# TM_Acondicionation.net
KiCad netlist of a schematic drawn in Altium Designer
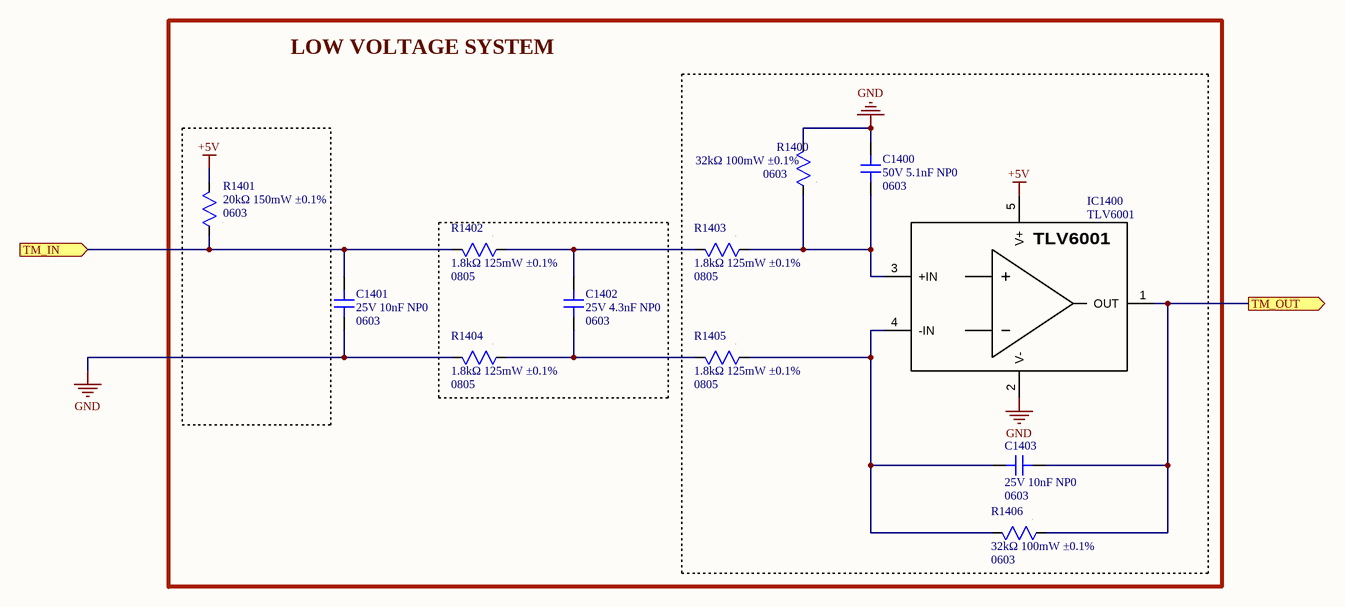
[diagram p0: TM_Acondicionation.SchDoc]

(export (version "E")
  (design (tool "Eeschema 10.0.6"))
  (components
    (comp (ref "C1400")
      (value "50V 5.1nF NP0")
      (footprint "CAP SMD 0603")
      (description "Condensadores de cerámica multicapa (MLCC- SMD/SMT) 50V 5100pF 0603 C0G 1%")
      (fields
        (field (name "PACKAGE") "0603")
        (field (name "MPN") "C0603C512F5GACTU")
        (field (name "MANUFACTURER") "KEMET")
      )
      (libsource (lib "eUSR_Database") (part "CAP non polarized"))
    )
    (comp (ref "C1401")
      (value "25V 10nF NP0")
      (footprint "CAP SMD 0603")
      (description "Condensadores de cerámica multicapa (MLCC- SMD/SMT) 50V 5100pF 0603 C0G 1%")
      (fields
        (field (name "PACKAGE") "0603")
        (field (name "MPN") "C0603C512F5GACTU")
        (field (name "MANUFACTURER") "KEMET")
      )
      (libsource (lib "eUSR_Database") (part "CAP non polarized"))
    )
    (comp (ref "C1402")
      (value "25V 4.3nF NP0")
      (footprint "CAP SMD 0603")
      (description "Condensadores de cerámica multicapa (MLCC- SMD/SMT) 4300 pF 25 VDC 2% 0603 C0G (NP0)")
      (fields
        (field (name "PACKAGE") "0603")
        (field (name "MPN") "GRM1885C1E432GA01J")
        (field (name "MANUFACTURER") "muRata")
      )
      (libsource (lib "eUSR_Database") (part "CAP non polarized"))
    )
    (comp (ref "C1403")
      (value "25V 10nF NP0")
      (footprint "CAP SMD 0603")
      (description "Condensadores de cerámica multicapa (MLCC- SMD/SMT) 0.01 uF 25 VDC 1% 0603 C0G (NP0) AEC-Q200")
      (fields
        (field (name "PACKAGE") "0603")
        (field (name "MPN") "GRT1885C1E103FA02D")
        (field (name "MANUFACTURER") "muRata")
      )
      (libsource (lib "eUSR_Database") (part "CAP non polarized"))
    )
    (comp (ref "IC1400")
      (value "TLV6001")
      (footprint "SOT-23-5")
      (fields (field (name "MPN") "TLV6001UIDBVR") (field (name "MANUFACTURER") "Texas Instruments"))
      (libsource (lib "eUSR_Database") (part "TLV6001"))
    )
    (comp (ref "R1400")
      (value "32kΩ 100mW ±0.1%")
      (footprint "RES SMD 0603")
      (description "Resistores de película fina - SMD 1/10W 32K Ohms 0.1%")
      (fields
        (field (name "PACKAGE") "0603")
        (field (name "MPN") "RT0603BRD0732KL")
        (field (name "MANUFACTURER") "YAGEO")
      )
      (libsource (lib "eUSR_Database") (part "RES"))
    )
    (comp (ref "R1401")
      (value "20kΩ 150mW ±0.1%")
      (footprint "RES SMD 0603")
      (description "Resistores de película fina - SMD RQ 0603 20K 0.1% 10PPM 5K RL")
      (fields
        (field (name "PACKAGE") "0603")
        (field (name "MPN") "RQ73C1J20KBTD")
        (field (name "MANUFACTURER") "TE Connectivity / Holsworthy")
      )
      (libsource (lib "eUSR_Database") (part "RES"))
    )
    (comp (ref "R1402")
      (value "1.8kΩ 125mW ±0.1%")
      (footprint "RES SMD 0805")
      (description "Thin Film Resistors 0805 1.8Kohm 0.1% 10ppm AEC-Q200")
      (fields
        (field (name "PACKAGE") "0805")
        (field (name "MPN") "ERA-6ARB182V")
        (field (name "MANUFACTURER") "Panasonic")
      )
      (libsource (lib "eUSR_Database") (part "RES"))
    )
    (comp (ref "R1403")
      (value "1.8kΩ 125mW ±0.1%")
      (footprint "RES SMD 0805")
      (description "Thin Film Resistors 0805 1.8Kohm 0.1% 10ppm AEC-Q200")
      (fields
        (field (name "PACKAGE") "0805")
        (field (name "MPN") "ERA-6ARB182V")
        (field (name "MANUFACTURER") "Panasonic")
      )
      (libsource (lib "eUSR_Database") (part "RES"))
    )
    (comp (ref "R1404")
      (value "1.8kΩ 125mW ±0.1%")
      (footprint "RES SMD 0805")
      (description "Thin Film Resistors 0805 1.8Kohm 0.1% 10ppm AEC-Q200")
      (fields
        (field (name "PACKAGE") "0805")
        (field (name "MPN") "ERA-6ARB182V")
        (field (name "MANUFACTURER") "Panasonic")
      )
      (libsource (lib "eUSR_Database") (part "RES"))
    )
    (comp (ref "R1405")
      (value "1.8kΩ 125mW ±0.1%")
      (footprint "RES SMD 0805")
      (description "Thin Film Resistors 0805 1.8Kohm 0.1% 10ppm AEC-Q200")
      (fields
        (field (name "PACKAGE") "0805")
        (field (name "MPN") "ERA-6ARB182V")
        (field (name "MANUFACTURER") "Panasonic")
      )
      (libsource (lib "eUSR_Database") (part "RES"))
    )
    (comp (ref "R1406")
      (value "32kΩ 100mW ±0.1%")
      (footprint "RES SMD 0603")
      (description "Resistores de película fina - SMD 1/10W 32K Ohms 0.1%")
      (fields
        (field (name "PACKAGE") "0603")
        (field (name "MPN") "RT0603BRD0732KL")
        (field (name "MANUFACTURER") "YAGEO")
      )
      (libsource (lib "eUSR_Database") (part "RES"))
    )
  )
  (nets
    (net (code "1") (name "+5V") (class "Default")
      (node (ref "IC1400") (pin "5") (pinfunction "V+_5") (pintype "passive"))
      (node (ref "R1401") (pin "2") (pinfunction "2_2") (pintype "passive"))
    )
    (net (code "2") (name "/TM_IN") (class "Default")
      (node (ref "C1401") (pin "1") (pinfunction "1_1") (pintype "passive"))
      (node (ref "R1401") (pin "1") (pinfunction "1_1") (pintype "passive"))
      (node (ref "R1402") (pin "2") (pinfunction "2_2") (pintype "passive"))
    )
    (net (code "3") (name "/TM_OUT") (class "Default")
      (node (ref "C1403") (pin "2") (pinfunction "2_2") (pintype "passive"))
      (node (ref "IC1400") (pin "1") (pinfunction "OUT_1") (pintype "passive"))
      (node (ref "R1406") (pin "1") (pinfunction "1_1") (pintype "passive"))
    )
    (net (code "4") (name "GND") (class "Default")
      (node (ref "C1400") (pin "1") (pinfunction "1_1") (pintype "passive"))
      (node (ref "C1401") (pin "2") (pinfunction "2_2") (pintype "passive"))
      (node (ref "IC1400") (pin "2") (pinfunction "V-_2") (pintype "passive"))
      (node (ref "R1400") (pin "2") (pinfunction "2_2") (pintype "passive"))
      (node (ref "R1404") (pin "2") (pinfunction "2_2") (pintype "passive"))
    )
    (net (code "5") (name "Net-(C1402-Pad1)") (class "Default")
      (node (ref "C1402") (pin "1") (pinfunction "1_1") (pintype "passive"))
      (node (ref "R1402") (pin "1") (pinfunction "1_1") (pintype "passive"))
      (node (ref "R1403") (pin "2") (pinfunction "2_2") (pintype "passive"))
    )
    (net (code "6") (name "Net-(C1402-Pad2)") (class "Default")
      (node (ref "C1402") (pin "2") (pinfunction "2_2") (pintype "passive"))
      (node (ref "R1404") (pin "1") (pinfunction "1_1") (pintype "passive"))
      (node (ref "R1405") (pin "2") (pinfunction "2_2") (pintype "passive"))
    )
    (net (code "7") (name "Net-(IC1400-+IN)") (class "Default")
      (node (ref "C1400") (pin "2") (pinfunction "2_2") (pintype "passive"))
      (node (ref "IC1400") (pin "3") (pinfunction "+IN_3") (pintype "passive"))
      (node (ref "R1400") (pin "1") (pinfunction "1_1") (pintype "passive"))
      (node (ref "R1403") (pin "1") (pinfunction "1_1") (pintype "passive"))
    )
    (net (code "8") (name "Net-(IC1400--IN)") (class "Default")
      (node (ref "C1403") (pin "1") (pinfunction "1_1") (pintype "passive"))
      (node (ref "IC1400") (pin "4") (pinfunction "-IN_4") (pintype "passive"))
      (node (ref "R1405") (pin "1") (pinfunction "1_1") (pintype "passive"))
      (node (ref "R1406") (pin "2") (pinfunction "2_2") (pintype "passive"))
    )
  )
)
